# activity_tracker_tester.net
KiCad netlist of a schematic drawn in Altium Designer
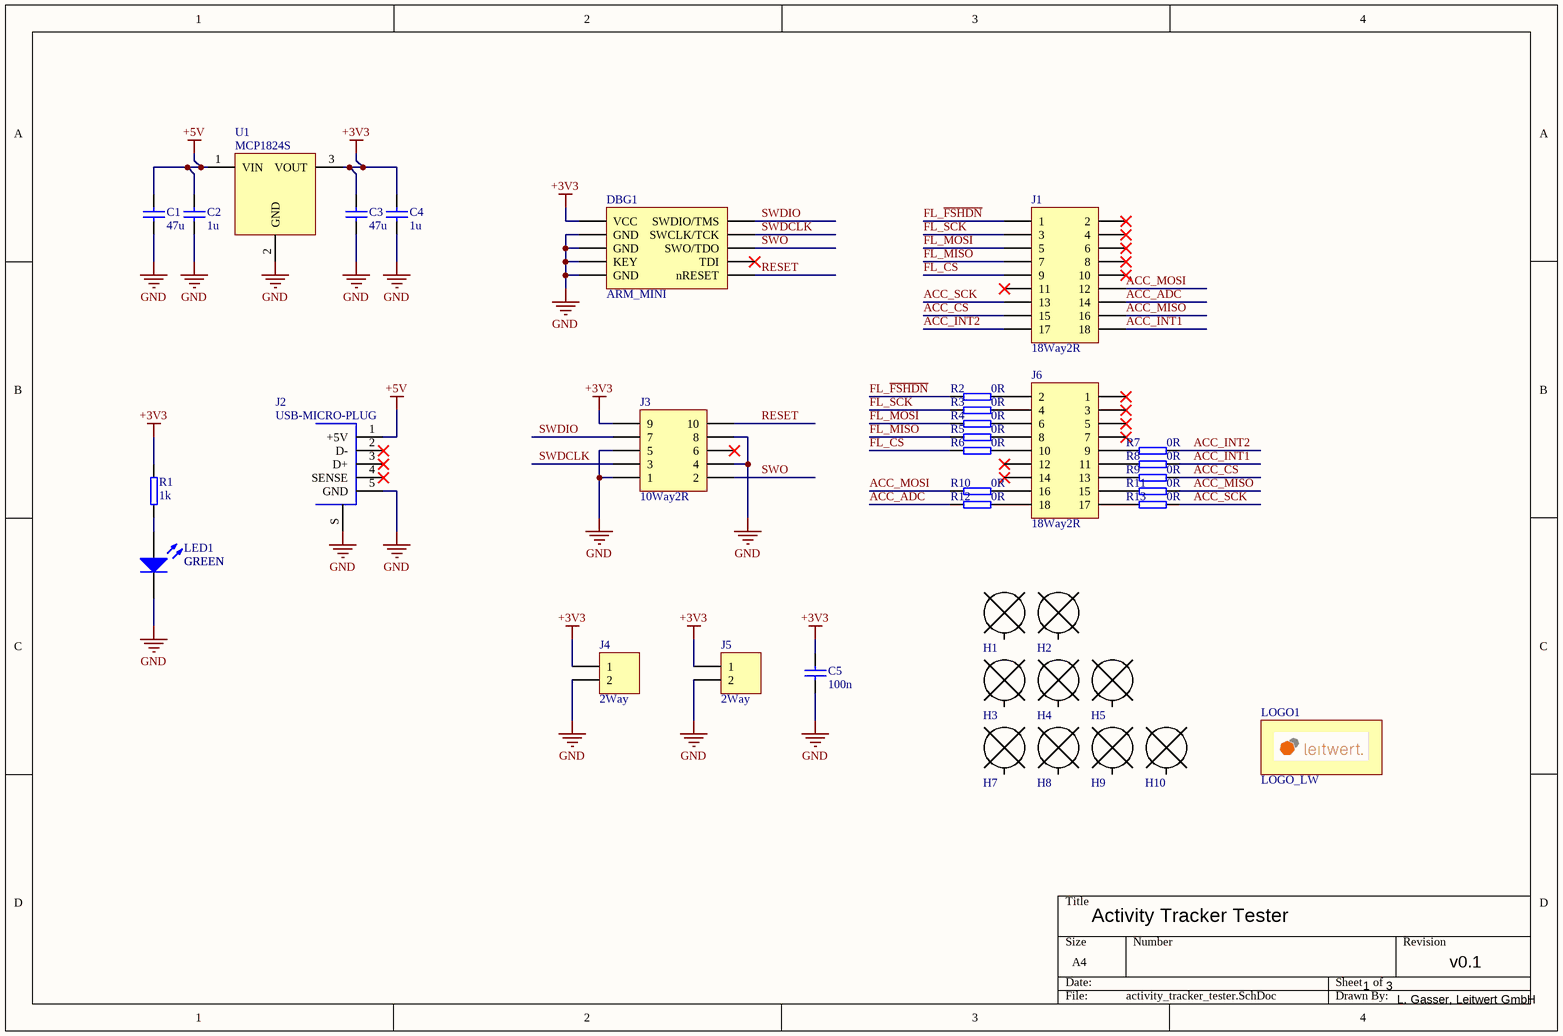
[diagram p0: activity_tracker_tester.SchDoc]

(export (version "E")
  (design (tool "Eeschema 10.0.6"))
  (components
    (comp (ref "C1")
      (value "47u")
      (footprint "CAPC3216X18N")
      (description "Capacitor")
      (fields (field (name "VOLTAGE") "6.3V"))
      (libsource (lib "rlc") (part "C"))
    )
    (comp (ref "C2")
      (value "1u")
      (footprint "CAPC1608X95N")
      (description "Capacitor")
      (fields (field (name "VOLTAGE") "10V"))
      (libsource (lib "rlc") (part "C"))
    )
    (comp (ref "C3")
      (value "47u")
      (footprint "CAPC3216X18N")
      (description "Capacitor")
      (fields (field (name "VOLTAGE") "6.3V"))
      (libsource (lib "rlc") (part "C"))
    )
    (comp (ref "C4")
      (value "1u")
      (footprint "CAPC1608X95N")
      (description "Capacitor")
      (fields (field (name "VOLTAGE") "10V"))
      (libsource (lib "rlc") (part "C"))
    )
    (comp (ref "C5")
      (value "100n")
      (footprint "CAPC1608X95N")
      (description "Capacitor")
      (fields (field (name "VOLTAGE") "10V"))
      (libsource (lib "rlc") (part "C"))
    )
    (comp (ref "DBG1")
      (value "ARM_MINI")
      (footprint "R127_M50-3500542")
      (description "ARM Mini JTAG / SWD 10-pin connector")
      (libsource (lib "icsp_debug-connectors") (part "ARM_MINI"))
    )
    (comp (ref "H1")
      (value "HOLE")
      (footprint "M1_SMALL")
      (description "Hole")
      (libsource (lib "misc") (part "HOLE"))
    )
    (comp (ref "H2")
      (value "HOLE")
      (footprint "M1_SMALL")
      (description "Hole")
      (libsource (lib "misc") (part "HOLE"))
    )
    (comp (ref "H3")
      (value "HOLE")
      (footprint "M1_SMALL_NOKEEPOUT")
      (description "Hole")
      (libsource (lib "misc") (part "HOLE"))
    )
    (comp (ref "H4")
      (value "HOLE")
      (footprint "M1_SMALL_NOKEEPOUT")
      (description "Hole")
      (libsource (lib "misc") (part "HOLE"))
    )
    (comp (ref "H5")
      (value "HOLE")
      (footprint "M1_SMALL_NOKEEPOUT")
      (description "Hole")
      (libsource (lib "misc") (part "HOLE"))
    )
    (comp (ref "H7")
      (value "HOLE")
      (footprint "M3_PLATED_MEDIUM")
      (description "Hole")
      (libsource (lib "misc") (part "HOLE"))
    )
    (comp (ref "H8")
      (value "HOLE")
      (footprint "M3_PLATED_MEDIUM")
      (description "Hole")
      (libsource (lib "misc") (part "HOLE"))
    )
    (comp (ref "H9")
      (value "HOLE")
      (footprint "M3_PLATED_MEDIUM")
      (description "Hole")
      (libsource (lib "misc") (part "HOLE"))
    )
    (comp (ref "H10")
      (value "HOLE")
      (footprint "M3_PLATED_MEDIUM")
      (description "Hole")
      (libsource (lib "misc") (part "HOLE"))
    )
    (comp (ref "J1")
      (value "18Way2R")
      (footprint "THT_2x9_R254")
      (description "18 Way 2 Row Connector")
      (libsource (lib "") (part "18Way2R_1"))
    )
    (comp (ref "J2")
      (value "USB-MICRO-PLUG")
      (footprint "475890001")
      (description "USB Micro Plug")
      (libsource (lib "connector") (part "USB-MICRO-PLUG"))
    )
    (comp (ref "J3")
      (value "10Way2R")
      (footprint "R127_M50-3500542")
      (description "10 Way 2 Row Connector")
      (libsource (lib "connector") (part "10Way2R"))
    )
    (comp (ref "J4")
      (value "2Way")
      (footprint "2PINR254")
      (description "2 Way Connector")
      (libsource (lib "connector") (part "2Way"))
    )
    (comp (ref "J5")
      (value "2Way")
      (footprint "2PINR254")
      (description "2 Way Connector")
      (libsource (lib "connector") (part "2Way"))
    )
    (comp (ref "J6")
      (value "18Way2R")
      (footprint "R127_M50-3500942")
      (description "18 Way 2 Row Connector")
      (libsource (lib "connector") (part "18Way2R"))
    )
    (comp (ref "LED1")
      (value "GREEN")
      (footprint "LED0603")
      (description "LED")
      (fields (field (name "COLOR") "GREEN"))
      (libsource (lib "led") (part "LED"))
    )
    (comp (ref "LOGO1")
      (value "LOGO_LW")
      (footprint "LW_MWOB_30MM_BW_VEC")
      (description "Leitwert Logo")
      (libsource (lib "logos") (part "LOGO_LW"))
    )
    (comp (ref "R1")
      (value "1k")
      (footprint "RESC1608X55N")
      (description "Resistor")
      (libsource (lib "rlc") (part "R"))
    )
    (comp (ref "R2")
      (value "0R")
      (footprint "RESC1608X55N")
      (description "Resistor")
      (libsource (lib "rlc") (part "R"))
    )
    (comp (ref "R3")
      (value "0R")
      (footprint "RESC1608X55N")
      (description "Resistor")
      (libsource (lib "rlc") (part "R"))
    )
    (comp (ref "R4")
      (value "0R")
      (footprint "RESC1608X55N")
      (description "Resistor")
      (libsource (lib "rlc") (part "R"))
    )
    (comp (ref "R5")
      (value "0R")
      (footprint "RESC1608X55N")
      (description "Resistor")
      (libsource (lib "rlc") (part "R"))
    )
    (comp (ref "R6")
      (value "0R")
      (footprint "RESC1608X55N")
      (description "Resistor")
      (libsource (lib "rlc") (part "R"))
    )
    (comp (ref "R7")
      (value "0R")
      (footprint "RESC1608X55N")
      (description "Resistor")
      (libsource (lib "rlc") (part "R"))
    )
    (comp (ref "R8")
      (value "0R")
      (footprint "RESC1608X55N")
      (description "Resistor")
      (libsource (lib "rlc") (part "R"))
    )
    (comp (ref "R9")
      (value "0R")
      (footprint "RESC1608X55N")
      (description "Resistor")
      (libsource (lib "rlc") (part "R"))
    )
    (comp (ref "R10")
      (value "0R")
      (footprint "RESC1608X55N")
      (description "Resistor")
      (libsource (lib "rlc") (part "R"))
    )
    (comp (ref "R11")
      (value "0R")
      (footprint "RESC1608X55N")
      (description "Resistor")
      (libsource (lib "rlc") (part "R"))
    )
    (comp (ref "R12")
      (value "0R")
      (footprint "RESC1608X55N")
      (description "Resistor")
      (libsource (lib "rlc") (part "R"))
    )
    (comp (ref "R13")
      (value "0R")
      (footprint "RESC1608X55N")
      (description "Resistor")
      (libsource (lib "rlc") (part "R"))
    )
    (comp (ref "U1")
      (value "MCP1824S")
      (footprint "SOT223P700X180-4N")
      (description "300 mA, Low Voltage, Low Quiescent Current LDO Regulator")
      (libsource (lib "v-reg") (part "MCP1824S"))
    )
  )
  (nets
    (net (code "1") (name "+3V3") (class "Default")
      (node (ref "C3") (pin "2") (pinfunction "2_2") (pintype "passive"))
      (node (ref "C4") (pin "2") (pinfunction "2_2") (pintype "passive"))
      (node (ref "C5") (pin "2") (pinfunction "2_2") (pintype "passive"))
      (node (ref "DBG1") (pin "1") (pinfunction "VCC_1") (pintype "power_in"))
      (node (ref "J3") (pin "9") (pinfunction "9_9") (pintype "passive"))
      (node (ref "J4") (pin "1") (pinfunction "1_1") (pintype "passive"))
      (node (ref "J5") (pin "1") (pinfunction "1_1") (pintype "passive"))
      (node (ref "R1") (pin "2") (pinfunction "2_2") (pintype "passive"))
      (node (ref "U1") (pin "3") (pinfunction "VOUT_3") (pintype "power_in"))
    )
    (net (code "2") (name "+5V") (class "Default")
      (node (ref "C1") (pin "2") (pinfunction "2_2") (pintype "passive"))
      (node (ref "C2") (pin "2") (pinfunction "2_2") (pintype "passive"))
      (node (ref "J2") (pin "1") (pinfunction "+5V_1") (pintype "power_in"))
      (node (ref "U1") (pin "1") (pinfunction "VIN_1") (pintype "power_in"))
    )
    (net (code "3") (name "/ACC_ADC") (class "Default")
      (node (ref "J1") (pin "14") (pinfunction "14_14") (pintype "passive"))
      (node (ref "R12") (pin "1") (pinfunction "1_1") (pintype "passive"))
    )
    (net (code "4") (name "/ACC_INT1") (class "Default")
      (node (ref "J1") (pin "18") (pinfunction "18_18") (pintype "passive"))
      (node (ref "R8") (pin "2") (pinfunction "2_2") (pintype "passive"))
    )
    (net (code "5") (name "/ACC_INT2") (class "Default")
      (node (ref "J1") (pin "17") (pinfunction "17_17") (pintype "passive"))
      (node (ref "R7") (pin "2") (pinfunction "2_2") (pintype "passive"))
    )
    (net (code "6") (name "/ACC_MISO") (class "Default")
      (node (ref "J1") (pin "16") (pinfunction "16_16") (pintype "passive"))
      (node (ref "R11") (pin "2") (pinfunction "2_2") (pintype "passive"))
    )
    (net (code "7") (name "/ACC_MOSI") (class "Default")
      (node (ref "J1") (pin "12") (pinfunction "12_12") (pintype "passive"))
      (node (ref "R10") (pin "1") (pinfunction "1_1") (pintype "passive"))
    )
    (net (code "8") (name "/ACC_SCK") (class "Default")
      (node (ref "J1") (pin "13") (pinfunction "13_13") (pintype "passive"))
      (node (ref "R13") (pin "2") (pinfunction "2_2") (pintype "passive"))
    )
    (net (code "9") (name "/ACC_~{CS}") (class "Default")
      (node (ref "J1") (pin "15") (pinfunction "15_15") (pintype "passive"))
      (node (ref "R9") (pin "2") (pinfunction "2_2") (pintype "passive"))
    )
    (net (code "10") (name "/FL_MISO") (class "Default")
      (node (ref "J1") (pin "7") (pinfunction "7_7") (pintype "passive"))
      (node (ref "R5") (pin "1") (pinfunction "1_1") (pintype "passive"))
    )
    (net (code "11") (name "/FL_MOSI") (class "Default")
      (node (ref "J1") (pin "5") (pinfunction "5_5") (pintype "passive"))
      (node (ref "R4") (pin "1") (pinfunction "1_1") (pintype "passive"))
    )
    (net (code "12") (name "/FL_SCK") (class "Default")
      (node (ref "J1") (pin "3") (pinfunction "3_3") (pintype "passive"))
      (node (ref "R3") (pin "1") (pinfunction "1_1") (pintype "passive"))
    )
    (net (code "13") (name "/FL_~{CS}") (class "Default")
      (node (ref "J1") (pin "9") (pinfunction "9_9") (pintype "passive"))
      (node (ref "R6") (pin "1") (pinfunction "1_1") (pintype "passive"))
    )
    (net (code "14") (name "/FL_~{FSHDN}") (class "Default")
      (node (ref "J1") (pin "1") (pinfunction "1_1") (pintype "passive"))
      (node (ref "R2") (pin "1") (pinfunction "1_1") (pintype "passive"))
    )
    (net (code "15") (name "/RESET") (class "Default")
      (node (ref "DBG1") (pin "10") (pinfunction "nRESET_10") (pintype "passive"))
      (node (ref "J3") (pin "10") (pinfunction "10_10") (pintype "passive"))
    )
    (net (code "16") (name "/SWDCLK") (class "Default")
      (node (ref "DBG1") (pin "4") (pinfunction "SWCLK/TCK_4") (pintype "passive"))
      (node (ref "J3") (pin "3") (pinfunction "3_3") (pintype "passive"))
    )
    (net (code "17") (name "/SWDIO") (class "Default")
      (node (ref "DBG1") (pin "2") (pinfunction "SWDIO/TMS_2") (pintype "passive"))
      (node (ref "J3") (pin "7") (pinfunction "7_7") (pintype "passive"))
    )
    (net (code "18") (name "/SWO") (class "Default")
      (node (ref "DBG1") (pin "6") (pinfunction "SWO/TDO_6") (pintype "passive"))
      (node (ref "J3") (pin "2") (pinfunction "2_2") (pintype "passive"))
    )
    (net (code "19") (name "GND") (class "Default")
      (node (ref "C1") (pin "1") (pinfunction "1_1") (pintype "passive"))
      (node (ref "C2") (pin "1") (pinfunction "1_1") (pintype "passive"))
      (node (ref "C3") (pin "1") (pinfunction "1_1") (pintype "passive"))
      (node (ref "C4") (pin "1") (pinfunction "1_1") (pintype "passive"))
      (node (ref "C5") (pin "1") (pinfunction "1_1") (pintype "passive"))
      (node (ref "DBG1") (pin "3") (pinfunction "GND_3") (pintype "power_in"))
      (node (ref "DBG1") (pin "5") (pinfunction "GND_5") (pintype "power_in"))
      (node (ref "DBG1") (pin "7") (pinfunction "KEY_7") (pintype "passive"))
      (node (ref "DBG1") (pin "9") (pinfunction "GND_9") (pintype "power_in"))
      (node (ref "J2") (pin "5") (pinfunction "GND_5") (pintype "power_in"))
      (node (ref "J2") (pin "S") (pinfunction "SHIELD_S") (pintype "passive"))
      (node (ref "J3") (pin "1") (pinfunction "1_1") (pintype "passive"))
      (node (ref "J3") (pin "4") (pinfunction "4_4") (pintype "passive"))
      (node (ref "J3") (pin "5") (pinfunction "5_5") (pintype "passive"))
      (node (ref "J3") (pin "8") (pinfunction "8_8") (pintype "passive"))
      (node (ref "J4") (pin "2") (pinfunction "2_2") (pintype "passive"))
      (node (ref "J5") (pin "2") (pinfunction "2_2") (pintype "passive"))
      (node (ref "LED1") (pin "2") (pinfunction "K_2") (pintype "passive"))
      (node (ref "U1") (pin "2") (pinfunction "GND_2") (pintype "power_in"))
    )
    (net (code "20") (name "Net-(J6-Pad2)") (class "Default")
      (node (ref "J6") (pin "2") (pinfunction "2_2") (pintype "passive"))
      (node (ref "R2") (pin "2") (pinfunction "2_2") (pintype "passive"))
    )
    (net (code "21") (name "Net-(J6-Pad4)") (class "Default")
      (node (ref "J6") (pin "4") (pinfunction "4_4") (pintype "passive"))
      (node (ref "R3") (pin "2") (pinfunction "2_2") (pintype "passive"))
    )
    (net (code "22") (name "Net-(J6-Pad6)") (class "Default")
      (node (ref "J6") (pin "6") (pinfunction "6_6") (pintype "passive"))
      (node (ref "R4") (pin "2") (pinfunction "2_2") (pintype "passive"))
    )
    (net (code "23") (name "Net-(J6-Pad8)") (class "Default")
      (node (ref "J6") (pin "8") (pinfunction "8_8") (pintype "passive"))
      (node (ref "R5") (pin "2") (pinfunction "2_2") (pintype "passive"))
    )
    (net (code "24") (name "Net-(J6-Pad9)") (class "Default")
      (node (ref "J6") (pin "9") (pinfunction "9_9") (pintype "passive"))
      (node (ref "R7") (pin "1") (pinfunction "1_1") (pintype "passive"))
    )
    (net (code "25") (name "Net-(J6-Pad10)") (class "Default")
      (node (ref "J6") (pin "10") (pinfunction "10_10") (pintype "passive"))
      (node (ref "R6") (pin "2") (pinfunction "2_2") (pintype "passive"))
    )
    (net (code "26") (name "Net-(J6-Pad11)") (class "Default")
      (node (ref "J6") (pin "11") (pinfunction "11_11") (pintype "passive"))
      (node (ref "R8") (pin "1") (pinfunction "1_1") (pintype "passive"))
    )
    (net (code "27") (name "Net-(J6-Pad13)") (class "Default")
      (node (ref "J6") (pin "13") (pinfunction "13_13") (pintype "passive"))
      (node (ref "R9") (pin "1") (pinfunction "1_1") (pintype "passive"))
    )
    (net (code "28") (name "Net-(J6-Pad15)") (class "Default")
      (node (ref "J6") (pin "15") (pinfunction "15_15") (pintype "passive"))
      (node (ref "R11") (pin "1") (pinfunction "1_1") (pintype "passive"))
    )
    (net (code "29") (name "Net-(J6-Pad16)") (class "Default")
      (node (ref "J6") (pin "16") (pinfunction "16_16") (pintype "passive"))
      (node (ref "R10") (pin "2") (pinfunction "2_2") (pintype "passive"))
    )
    (net (code "30") (name "Net-(J6-Pad17)") (class "Default")
      (node (ref "J6") (pin "17") (pinfunction "17_17") (pintype "passive"))
      (node (ref "R13") (pin "1") (pinfunction "1_1") (pintype "passive"))
    )
    (net (code "31") (name "Net-(J6-Pad18)") (class "Default")
      (node (ref "J6") (pin "18") (pinfunction "18_18") (pintype "passive"))
      (node (ref "R12") (pin "2") (pinfunction "2_2") (pintype "passive"))
    )
    (net (code "32") (name "Net-(LED1-A)") (class "Default")
      (node (ref "LED1") (pin "1") (pinfunction "A_1") (pintype "passive"))
      (node (ref "R1") (pin "1") (pinfunction "1_1") (pintype "passive"))
    )
    (net (code "33") (name "unconnected-(DBG1-TDI-Pad8)") (class "Default")
      (node (ref "DBG1") (pin "8") (pinfunction "TDI_8") (pintype "passive+no_connect"))
    )
    (net (code "34") (name "unconnected-(H1-PadH)") (class "Default")
      (node (ref "H1") (pin "H") (pinfunction "H_H") (pintype "passive"))
    )
    (net (code "35") (name "unconnected-(H2-PadH)") (class "Default")
      (node (ref "H2") (pin "H") (pinfunction "H_H") (pintype "passive"))
    )
    (net (code "36") (name "unconnected-(H3-PadH)") (class "Default")
      (node (ref "H3") (pin "H") (pinfunction "H_H") (pintype "passive"))
    )
    (net (code "37") (name "unconnected-(H4-PadH)") (class "Default")
      (node (ref "H4") (pin "H") (pinfunction "H_H") (pintype "passive"))
    )
    (net (code "38") (name "unconnected-(H5-PadH)") (class "Default")
      (node (ref "H5") (pin "H") (pinfunction "H_H") (pintype "passive"))
    )
    (net (code "39") (name "unconnected-(H7-PadH)") (class "Default")
      (node (ref "H7") (pin "H") (pinfunction "H_H") (pintype "passive"))
    )
    (net (code "40") (name "unconnected-(H8-PadH)") (class "Default")
      (node (ref "H8") (pin "H") (pinfunction "H_H") (pintype "passive"))
    )
    (net (code "41") (name "unconnected-(H9-PadH)") (class "Default")
      (node (ref "H9") (pin "H") (pinfunction "H_H") (pintype "passive"))
    )
    (net (code "42") (name "unconnected-(H10-PadH)") (class "Default")
      (node (ref "H10") (pin "H") (pinfunction "H_H") (pintype "passive"))
    )
    (net (code "43") (name "unconnected-(J1-Pad2)") (class "Default")
      (node (ref "J1") (pin "2") (pinfunction "2_2") (pintype "passive+no_connect"))
    )
    (net (code "44") (name "unconnected-(J1-Pad4)") (class "Default")
      (node (ref "J1") (pin "4") (pinfunction "4_4") (pintype "passive+no_connect"))
    )
    (net (code "45") (name "unconnected-(J1-Pad6)") (class "Default")
      (node (ref "J1") (pin "6") (pinfunction "6_6") (pintype "passive+no_connect"))
    )
    (net (code "46") (name "unconnected-(J1-Pad8)") (class "Default")
      (node (ref "J1") (pin "8") (pinfunction "8_8") (pintype "passive+no_connect"))
    )
    (net (code "47") (name "unconnected-(J1-Pad10)") (class "Default")
      (node (ref "J1") (pin "10") (pinfunction "10_10") (pintype "passive+no_connect"))
    )
    (net (code "48") (name "unconnected-(J1-Pad11)") (class "Default")
      (node (ref "J1") (pin "11") (pinfunction "11_11") (pintype "passive+no_connect"))
    )
    (net (code "49") (name "unconnected-(J2-D+-Pad3)") (class "Default")
      (node (ref "J2") (pin "3") (pinfunction "D+_3") (pintype "passive+no_connect"))
    )
    (net (code "50") (name "unconnected-(J2-D--Pad2)") (class "Default")
      (node (ref "J2") (pin "2") (pinfunction "D-_2") (pintype "passive+no_connect"))
    )
    (net (code "51") (name "unconnected-(J2-SENSE-Pad4)") (class "Default")
      (node (ref "J2") (pin "4") (pinfunction "SENSE_4") (pintype "power_in+no_connect"))
    )
    (net (code "52") (name "unconnected-(J3-Pad6)") (class "Default")
      (node (ref "J3") (pin "6") (pinfunction "6_6") (pintype "passive+no_connect"))
    )
    (net (code "53") (name "unconnected-(J6-Pad1)") (class "Default")
      (node (ref "J6") (pin "1") (pinfunction "1_1") (pintype "passive+no_connect"))
    )
    (net (code "54") (name "unconnected-(J6-Pad3)") (class "Default")
      (node (ref "J6") (pin "3") (pinfunction "3_3") (pintype "passive+no_connect"))
    )
    (net (code "55") (name "unconnected-(J6-Pad5)") (class "Default")
      (node (ref "J6") (pin "5") (pinfunction "5_5") (pintype "passive+no_connect"))
    )
    (net (code "56") (name "unconnected-(J6-Pad7)") (class "Default")
      (node (ref "J6") (pin "7") (pinfunction "7_7") (pintype "passive+no_connect"))
    )
    (net (code "57") (name "unconnected-(J6-Pad12)") (class "Default")
      (node (ref "J6") (pin "12") (pinfunction "12_12") (pintype "passive+no_connect"))
    )
    (net (code "58") (name "unconnected-(J6-Pad14)") (class "Default")
      (node (ref "J6") (pin "14") (pinfunction "14_14") (pintype "passive+no_connect"))
    )
  )
)
